# master_board.net
KiCad netlist of a schematic drawn in EAGLE
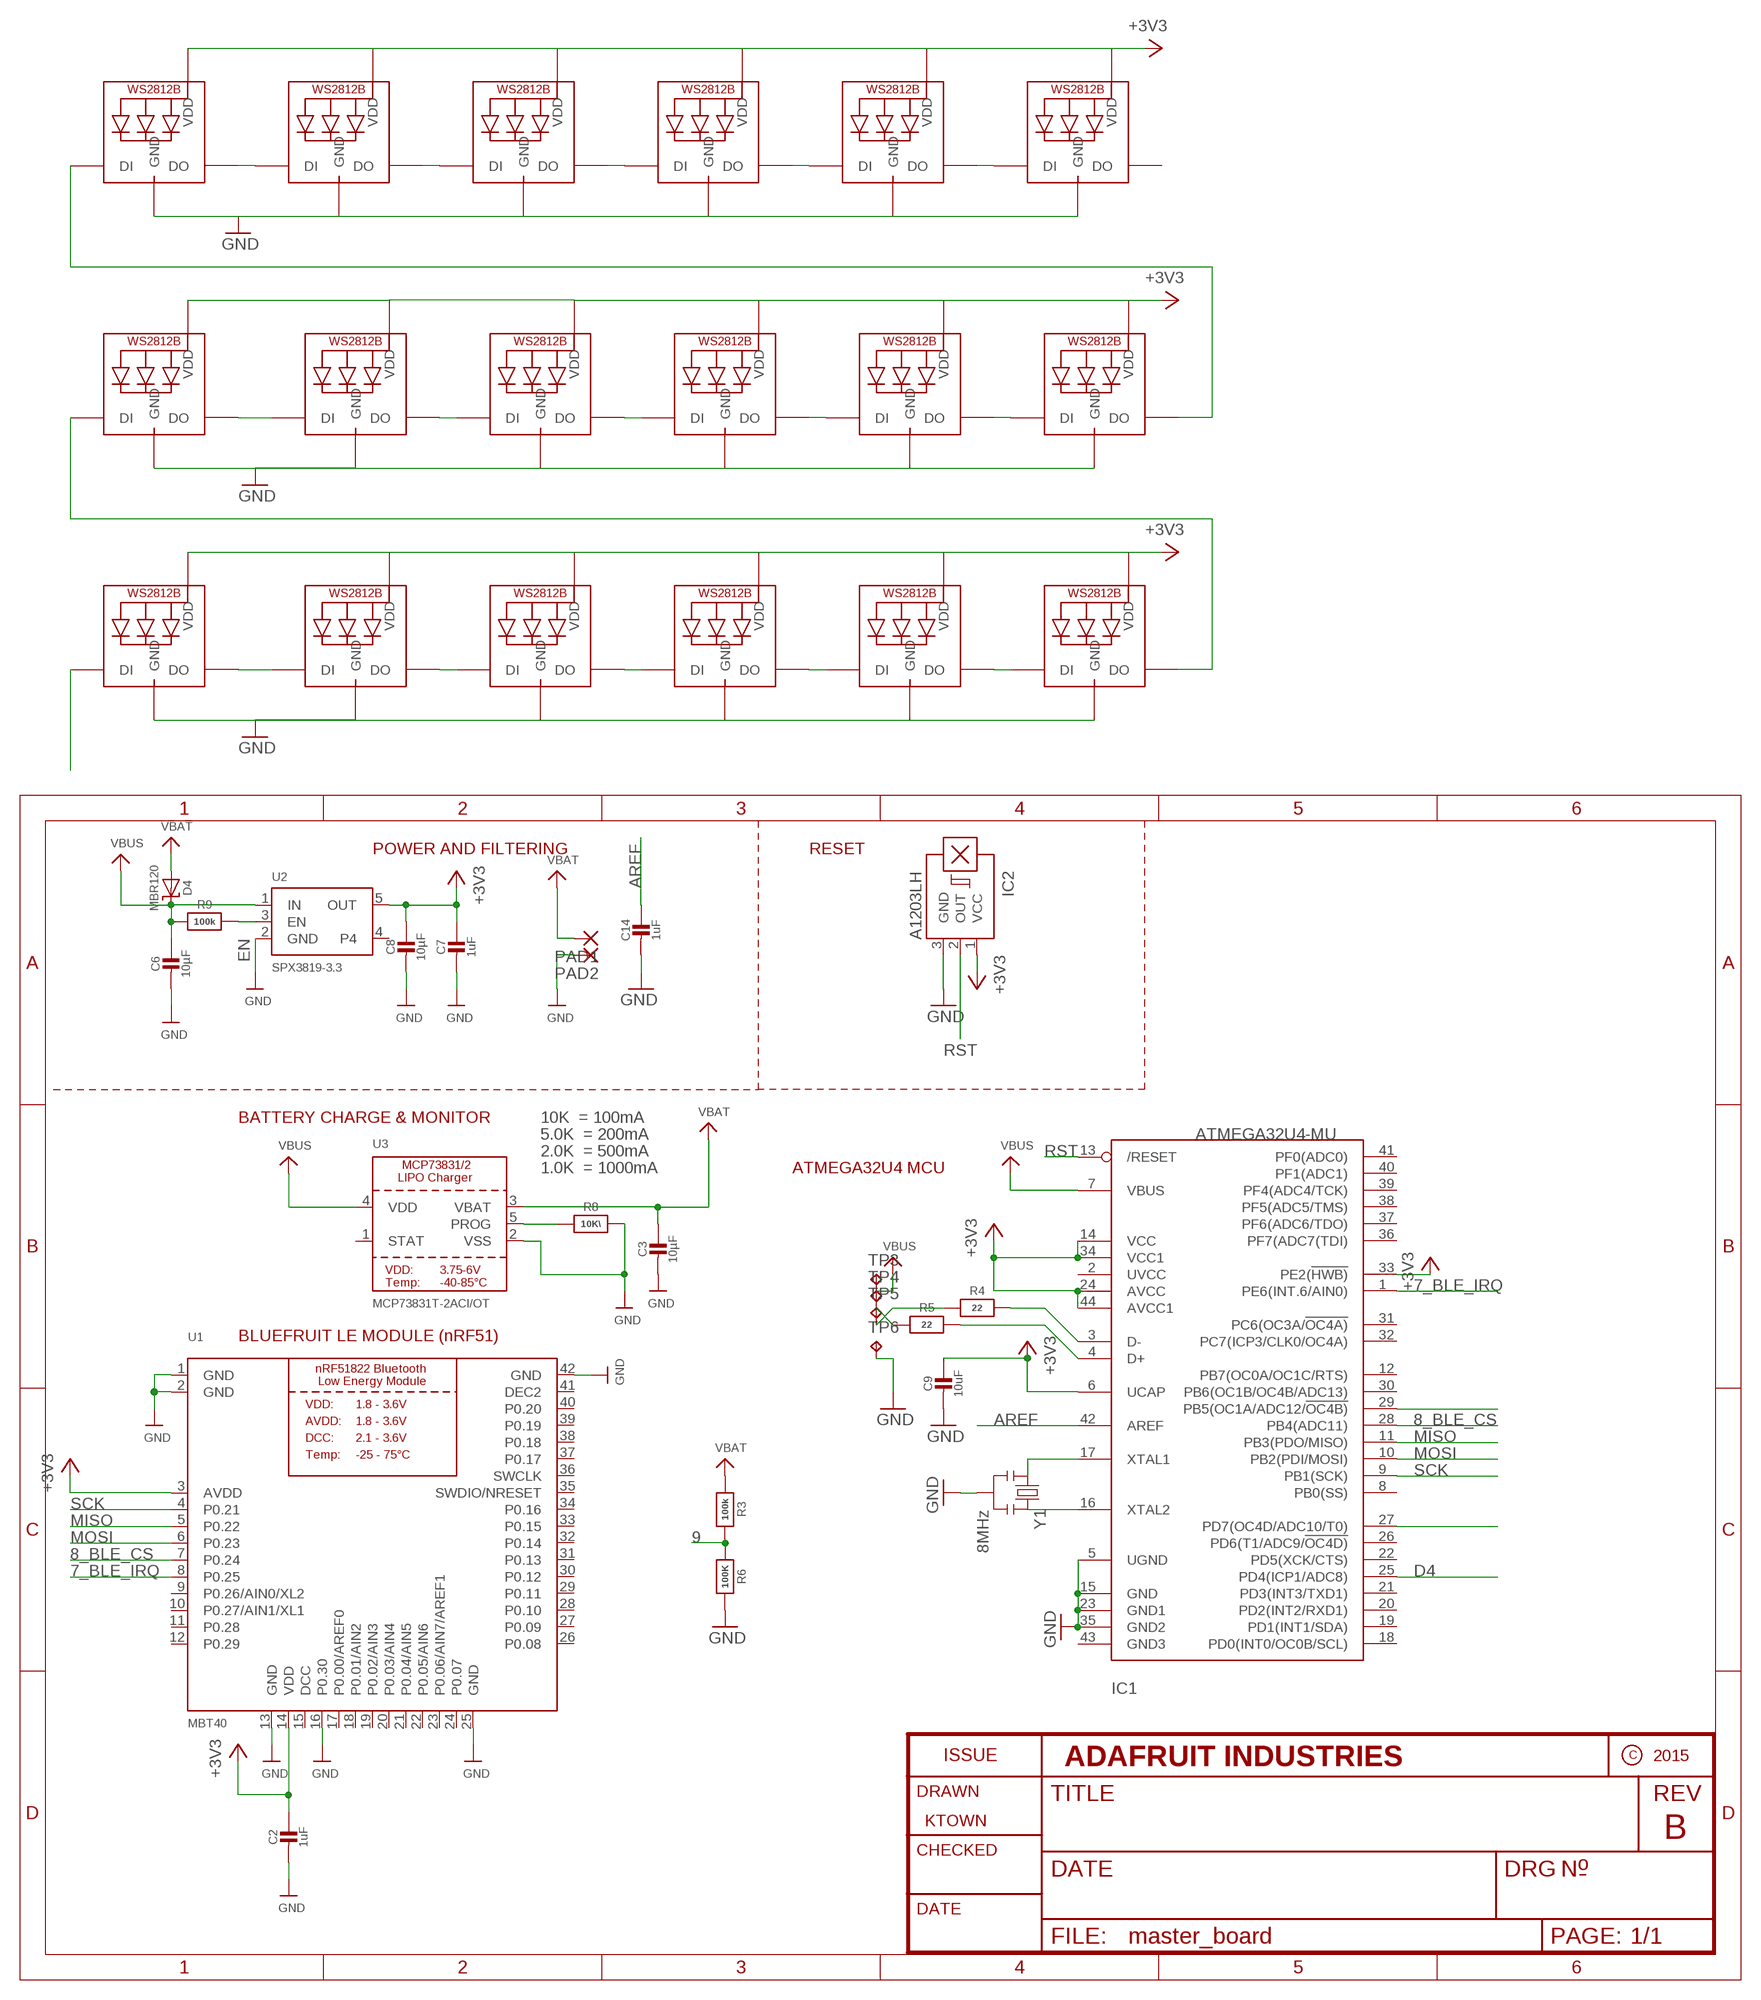
[diagram p0: schematic, sheet 1]

(export (version "E")
  (design (tool "Eeschema 10.0.6"))
  (components
    (comp (ref "C2")
      (value "1uF")
      (footprint "eagle-import:0805-NO")
      (libsource (lib "eagle-import") (part "CAP_CERAMIC0805-NOOUTLINE"))
    )
    (comp (ref "C3")
      (value "10µF")
      (footprint "eagle-import:0805-NO")
      (libsource (lib "eagle-import") (part "CAP_CERAMIC0805-NOOUTLINE"))
    )
    (comp (ref "C6")
      (value "10µF")
      (footprint "eagle-import:0805-NO")
      (libsource (lib "eagle-import") (part "CAP_CERAMIC0805-NOOUTLINE"))
    )
    (comp (ref "C7")
      (value "1uF")
      (footprint "eagle-import:0603-NO")
      (libsource (lib "eagle-import") (part "CAP_CERAMIC0603_NO"))
    )
    (comp (ref "C8")
      (value "10µF")
      (footprint "eagle-import:0805-NO")
      (libsource (lib "eagle-import") (part "CAP_CERAMIC0805-NOOUTLINE"))
    )
    (comp (ref "C9")
      (value "10uF")
      (footprint "eagle-import:0805-NO")
      (libsource (lib "eagle-import") (part "CAP_CERAMIC0805-NOOUTLINE"))
    )
    (comp (ref "C14")
      (value "1uF")
      (footprint "eagle-import:0603-NO")
      (libsource (lib "eagle-import") (part "CAP_CERAMIC0603_NO"))
    )
    (comp (ref "D4")
      (value "MBR120")
      (footprint "eagle-import:SOD-123")
      (libsource (lib "eagle-import") (part "DIODE-SCHOTTKYSOD-123"))
    )
    (comp (ref "IC1")
      (value "ATMEGA32U4-MU")
      (footprint "eagle-import:TQFN44_7MM")
      (libsource (lib "eagle-import") (part "ATMEGA32U4-MU"))
    )
    (comp (ref "IC2")
      (value "A1203LH")
      (footprint "eagle-import:SOT23-W")
      (fields (field (name "MF") "ALLEGRO MICROSYSTEMS, INC.") (field (name "MPN") "A1203LLHLT-T"))
      (libsource (lib "eagle-import") (part "A12?LH03"))
    )
    (comp (ref "LED1")
      (value "WS2812B3535")
      (footprint "eagle-import:LED3535")
      (libsource (lib "eagle-import") (part "WS2812B3535"))
    )
    (comp (ref "LED2")
      (value "WS2812B3535")
      (footprint "eagle-import:LED3535")
      (libsource (lib "eagle-import") (part "WS2812B3535"))
    )
    (comp (ref "LED3")
      (value "WS2812B3535")
      (footprint "eagle-import:LED3535")
      (libsource (lib "eagle-import") (part "WS2812B3535"))
    )
    (comp (ref "LED4")
      (value "WS2812B3535")
      (footprint "eagle-import:LED3535")
      (libsource (lib "eagle-import") (part "WS2812B3535"))
    )
    (comp (ref "LED5")
      (value "WS2812B3535")
      (footprint "eagle-import:LED3535")
      (libsource (lib "eagle-import") (part "WS2812B3535"))
    )
    (comp (ref "LED6")
      (value "WS2812B3535")
      (footprint "eagle-import:LED3535")
      (libsource (lib "eagle-import") (part "WS2812B3535"))
    )
    (comp (ref "LED7")
      (value "WS2812B3535")
      (footprint "eagle-import:LED3535")
      (libsource (lib "eagle-import") (part "WS2812B3535"))
    )
    (comp (ref "LED8")
      (value "WS2812B3535")
      (footprint "eagle-import:LED3535")
      (libsource (lib "eagle-import") (part "WS2812B3535"))
    )
    (comp (ref "LED9")
      (value "WS2812B3535")
      (footprint "eagle-import:LED3535")
      (libsource (lib "eagle-import") (part "WS2812B3535"))
    )
    (comp (ref "LED10")
      (value "WS2812B3535")
      (footprint "eagle-import:LED3535")
      (libsource (lib "eagle-import") (part "WS2812B3535"))
    )
    (comp (ref "LED11")
      (value "WS2812B3535")
      (footprint "eagle-import:LED3535")
      (libsource (lib "eagle-import") (part "WS2812B3535"))
    )
    (comp (ref "LED12")
      (value "WS2812B3535")
      (footprint "eagle-import:LED3535")
      (libsource (lib "eagle-import") (part "WS2812B3535"))
    )
    (comp (ref "LED13")
      (value "WS2812B3535")
      (footprint "eagle-import:LED3535")
      (libsource (lib "eagle-import") (part "WS2812B3535"))
    )
    (comp (ref "LED14")
      (value "WS2812B3535")
      (footprint "eagle-import:LED3535")
      (libsource (lib "eagle-import") (part "WS2812B3535"))
    )
    (comp (ref "LED15")
      (value "WS2812B3535")
      (footprint "eagle-import:LED3535")
      (libsource (lib "eagle-import") (part "WS2812B3535"))
    )
    (comp (ref "LED16")
      (value "WS2812B3535")
      (footprint "eagle-import:LED3535")
      (libsource (lib "eagle-import") (part "WS2812B3535"))
    )
    (comp (ref "LED17")
      (value "WS2812B3535")
      (footprint "eagle-import:LED3535")
      (libsource (lib "eagle-import") (part "WS2812B3535"))
    )
    (comp (ref "LED18")
      (value "WS2812B3535")
      (footprint "eagle-import:LED3535")
      (libsource (lib "eagle-import") (part "WS2812B3535"))
    )
    (comp (ref "PAD1")
      (value "2,54/1,1")
      (footprint "eagle-import:2,54_1,1")
      (libsource (lib "eagle-import") (part "2,54/1,1"))
    )
    (comp (ref "PAD2")
      (value "2,54/1,1")
      (footprint "eagle-import:2,54_1,1")
      (libsource (lib "eagle-import") (part "2,54/1,1"))
    )
    (comp (ref "R3")
      (value "100k")
      (footprint "eagle-import:0603-NO")
      (libsource (lib "eagle-import") (part "RESISTOR_0603_NOOUT"))
    )
    (comp (ref "R4")
      (value "22")
      (footprint "eagle-import:0603-NO")
      (libsource (lib "eagle-import") (part "RESISTOR_0603_NOOUT"))
    )
    (comp (ref "R5")
      (value "22")
      (footprint "eagle-import:0603-NO")
      (libsource (lib "eagle-import") (part "RESISTOR_0603_NOOUT"))
    )
    (comp (ref "R6")
      (value "100K")
      (footprint "eagle-import:_0603MP")
      (libsource (lib "eagle-import") (part "RESISTOR_0603MP"))
    )
    (comp (ref "R8")
      (value "10K\\")
      (footprint "eagle-import:0603-NO")
      (libsource (lib "eagle-import") (part "RESISTOR_0603_NOOUT"))
    )
    (comp (ref "R9")
      (value "100k")
      (footprint "eagle-import:0603-NO")
      (libsource (lib "eagle-import") (part "RESISTOR_0603_NOOUT"))
    )
    (comp (ref "TP3")
      (value "TPTP06SQ")
      (footprint "eagle-import:TP06SQ")
      (libsource (lib "eagle-import") (part "TPTP06SQ"))
    )
    (comp (ref "TP4")
      (value "TPTP06SQ")
      (footprint "eagle-import:TP06SQ")
      (libsource (lib "eagle-import") (part "TPTP06SQ"))
    )
    (comp (ref "TP5")
      (value "TPTP06SQ")
      (footprint "eagle-import:TP06SQ")
      (libsource (lib "eagle-import") (part "TPTP06SQ"))
    )
    (comp (ref "TP6")
      (value "TPTP06SQ")
      (footprint "eagle-import:TP06SQ")
      (libsource (lib "eagle-import") (part "TPTP06SQ"))
    )
    (comp (ref "U1")
      (value "MBT40")
      (footprint "eagle-import:BLE_MODULE_RAYTAC_MDBT40")
      (libsource (lib "eagle-import") (part "NRF51822_MODULE_MDBT40"))
    )
    (comp (ref "U2")
      (value "SPX3819-3.3")
      (footprint "eagle-import:SOT23-5")
      (libsource (lib "eagle-import") (part "VREG_SOT23-5"))
    )
    (comp (ref "U3")
      (value "MCP73831T-2ACI/OT")
      (footprint "eagle-import:SOT23-5")
      (libsource (lib "eagle-import") (part "MCP73831/2"))
    )
    (comp (ref "Y1")
      (value "8MHz")
      (footprint "eagle-import:RESONATOR-SMD")
      (libsource (lib "eagle-import") (part "RESONATORSMD"))
    )
  )
  (nets
    (net (code "1") (name "+3V3") (class "Default")
      (node (ref "C2") (pin "1") (pinfunction "1_1") (pintype "passive"))
      (node (ref "C7") (pin "1") (pinfunction "1_1") (pintype "passive"))
      (node (ref "C8") (pin "1") (pinfunction "1_1") (pintype "passive"))
      (node (ref "C9") (pin "1") (pinfunction "1_1") (pintype "passive"))
      (node (ref "IC1") (pin "14") (pinfunction "VCC_14") (pintype "bidirectional"))
      (node (ref "IC1") (pin "24") (pinfunction "AVCC_24") (pintype "bidirectional"))
      (node (ref "IC1") (pin "33") (pinfunction "PE2(~{HWB})_33") (pintype "bidirectional"))
      (node (ref "IC1") (pin "34") (pinfunction "VCC1_34") (pintype "bidirectional"))
      (node (ref "IC1") (pin "44") (pinfunction "AVCC1_44") (pintype "bidirectional"))
      (node (ref "IC1") (pin "6") (pinfunction "UCAP_6") (pintype "bidirectional"))
      (node (ref "IC2") (pin "1") (pinfunction "VCC_1") (pintype "power_in"))
      (node (ref "LED1") (pin "2") (pinfunction "VDD_2") (pintype "power_in"))
      (node (ref "LED10") (pin "2") (pinfunction "VDD_2") (pintype "power_in"))
      (node (ref "LED11") (pin "2") (pinfunction "VDD_2") (pintype "power_in"))
      (node (ref "LED12") (pin "2") (pinfunction "VDD_2") (pintype "power_in"))
      (node (ref "LED13") (pin "2") (pinfunction "VDD_2") (pintype "power_in"))
      (node (ref "LED14") (pin "2") (pinfunction "VDD_2") (pintype "power_in"))
      (node (ref "LED15") (pin "2") (pinfunction "VDD_2") (pintype "power_in"))
      (node (ref "LED16") (pin "2") (pinfunction "VDD_2") (pintype "power_in"))
      (node (ref "LED17") (pin "2") (pinfunction "VDD_2") (pintype "power_in"))
      (node (ref "LED18") (pin "2") (pinfunction "VDD_2") (pintype "power_in"))
      (node (ref "LED2") (pin "2") (pinfunction "VDD_2") (pintype "power_in"))
      (node (ref "LED3") (pin "2") (pinfunction "VDD_2") (pintype "power_in"))
      (node (ref "LED4") (pin "2") (pinfunction "VDD_2") (pintype "power_in"))
      (node (ref "LED5") (pin "2") (pinfunction "VDD_2") (pintype "power_in"))
      (node (ref "LED6") (pin "2") (pinfunction "VDD_2") (pintype "power_in"))
      (node (ref "LED7") (pin "2") (pinfunction "VDD_2") (pintype "power_in"))
      (node (ref "LED8") (pin "2") (pinfunction "VDD_2") (pintype "power_in"))
      (node (ref "LED9") (pin "2") (pinfunction "VDD_2") (pintype "power_in"))
      (node (ref "U1") (pin "14") (pinfunction "VDD_14") (pintype "power_in"))
      (node (ref "U1") (pin "3") (pinfunction "AVDD_3") (pintype "power_in"))
      (node (ref "U2") (pin "5") (pinfunction "OUT_5") (pintype "power_in"))
    )
    (net (code "2") (name "/6") (class "Default")
      (node (ref "IC1") (pin "27") (pinfunction "PD7(OC4D/ADC10/T0)_27") (pintype "bidirectional"))
      (node (ref "LED1") (pin "1") (pinfunction "DI_1") (pintype "input"))
    )
    (net (code "3") (name "/7_BLE_IRQ") (class "Default")
      (node (ref "IC1") (pin "1") (pinfunction "PE6(INT.6/AIN0)_1") (pintype "bidirectional"))
      (node (ref "U1") (pin "8") (pinfunction "P0.25_8") (pintype "bidirectional"))
    )
    (net (code "4") (name "/8_BLE_CS") (class "Default")
      (node (ref "IC1") (pin "28") (pinfunction "PB4(ADC11)_28") (pintype "bidirectional"))
      (node (ref "U1") (pin "7") (pinfunction "P0.24_7") (pintype "bidirectional"))
    )
    (net (code "5") (name "/9") (class "Default")
      (node (ref "IC1") (pin "29") (pinfunction "PB5(OC1A/ADC12/~{OC4B})_29") (pintype "bidirectional"))
      (node (ref "R3") (pin "2") (pinfunction "2_2") (pintype "passive"))
      (node (ref "R6") (pin "1") (pinfunction "1_1") (pintype "passive"))
    )
    (net (code "6") (name "/AREF") (class "Default")
      (node (ref "C14") (pin "1") (pinfunction "1_1") (pintype "passive"))
      (node (ref "IC1") (pin "42") (pinfunction "AREF_42") (pintype "bidirectional"))
    )
    (net (code "7") (name "/D4") (class "Default")
      (node (ref "IC1") (pin "25") (pinfunction "PD4(ICP1/ADC8)_25") (pintype "bidirectional"))
    )
    (net (code "8") (name "/DCC") (class "Default")
      (node (ref "U1") (pin "15") (pinfunction "DCC_15") (pintype "power_in"))
    )
    (net (code "9") (name "/DEC2") (class "Default")
      (node (ref "U1") (pin "41") (pinfunction "DEC2_41") (pintype "power_in"))
    )
    (net (code "10") (name "/EN") (class "Default")
      (node (ref "R9") (pin "2") (pinfunction "2_2") (pintype "passive"))
      (node (ref "U2") (pin "3") (pinfunction "EN_3") (pintype "input"))
    )
    (net (code "11") (name "/MISO") (class "Default")
      (node (ref "IC1") (pin "11") (pinfunction "PB3(PDO/MISO)_11") (pintype "bidirectional"))
      (node (ref "U1") (pin "5") (pinfunction "P0.22_5") (pintype "bidirectional"))
    )
    (net (code "12") (name "/MOSI") (class "Default")
      (node (ref "IC1") (pin "10") (pinfunction "PB2(PDI/MOSI)_10") (pintype "bidirectional"))
      (node (ref "U1") (pin "6") (pinfunction "P0.23_6") (pintype "bidirectional"))
    )
    (net (code "13") (name "/RST") (class "Default")
      (node (ref "IC1") (pin "13") (pinfunction "/RESET_13") (pintype "bidirectional"))
      (node (ref "IC2") (pin "2") (pinfunction "OUT_2") (pintype "output"))
    )
    (net (code "14") (name "/SCK") (class "Default")
      (node (ref "IC1") (pin "9") (pinfunction "PB1(SCK)_9") (pintype "bidirectional"))
      (node (ref "U1") (pin "4") (pinfunction "P0.21_4") (pintype "bidirectional"))
    )
    (net (code "15") (name "GND") (class "Default")
      (node (ref "C14") (pin "2") (pinfunction "2_2") (pintype "passive"))
      (node (ref "C2") (pin "2") (pinfunction "2_2") (pintype "passive"))
      (node (ref "C3") (pin "2") (pinfunction "2_2") (pintype "passive"))
      (node (ref "C6") (pin "2") (pinfunction "2_2") (pintype "passive"))
      (node (ref "C7") (pin "2") (pinfunction "2_2") (pintype "passive"))
      (node (ref "C8") (pin "2") (pinfunction "2_2") (pintype "passive"))
      (node (ref "C9") (pin "2") (pinfunction "2_2") (pintype "passive"))
      (node (ref "IC1") (pin "15") (pinfunction "GND_15") (pintype "bidirectional"))
      (node (ref "IC1") (pin "23") (pinfunction "GND1_23") (pintype "bidirectional"))
      (node (ref "IC1") (pin "35") (pinfunction "GND2_35") (pintype "bidirectional"))
      (node (ref "IC1") (pin "5") (pinfunction "UGND_5") (pintype "bidirectional"))
      (node (ref "IC2") (pin "3") (pinfunction "GND_3") (pintype "power_in"))
      (node (ref "LED1") (pin "4") (pinfunction "GND_4") (pintype "power_in"))
      (node (ref "LED10") (pin "4") (pinfunction "GND_4") (pintype "power_in"))
      (node (ref "LED11") (pin "4") (pinfunction "GND_4") (pintype "power_in"))
      (node (ref "LED12") (pin "4") (pinfunction "GND_4") (pintype "power_in"))
      (node (ref "LED13") (pin "4") (pinfunction "GND_4") (pintype "power_in"))
      (node (ref "LED14") (pin "4") (pinfunction "GND_4") (pintype "power_in"))
      (node (ref "LED15") (pin "4") (pinfunction "GND_4") (pintype "power_in"))
      (node (ref "LED16") (pin "4") (pinfunction "GND_4") (pintype "power_in"))
      (node (ref "LED17") (pin "4") (pinfunction "GND_4") (pintype "power_in"))
      (node (ref "LED18") (pin "4") (pinfunction "GND_4") (pintype "power_in"))
      (node (ref "LED2") (pin "4") (pinfunction "GND_4") (pintype "power_in"))
      (node (ref "LED3") (pin "4") (pinfunction "GND_4") (pintype "power_in"))
      (node (ref "LED4") (pin "4") (pinfunction "GND_4") (pintype "power_in"))
      (node (ref "LED5") (pin "4") (pinfunction "GND_4") (pintype "power_in"))
      (node (ref "LED6") (pin "4") (pinfunction "GND_4") (pintype "power_in"))
      (node (ref "LED7") (pin "4") (pinfunction "GND_4") (pintype "power_in"))
      (node (ref "LED8") (pin "4") (pinfunction "GND_4") (pintype "power_in"))
      (node (ref "LED9") (pin "4") (pinfunction "GND_4") (pintype "power_in"))
      (node (ref "PAD2") (pin "1") (pinfunction "P_1") (pintype "passive"))
      (node (ref "R6") (pin "2") (pinfunction "2_2") (pintype "passive"))
      (node (ref "R8") (pin "2") (pinfunction "2_2") (pintype "passive"))
      (node (ref "TP6") (pin "TP") (pinfunction "TP_TP") (pintype "input"))
      (node (ref "U1") (pin "1") (pinfunction "GND_1") (pintype "power_in"))
      (node (ref "U1") (pin "13") (pinfunction "GND_13") (pintype "power_in"))
      (node (ref "U1") (pin "16") (pinfunction "P0.30_16") (pintype "bidirectional"))
      (node (ref "U1") (pin "2") (pinfunction "GND_2") (pintype "power_in"))
      (node (ref "U1") (pin "25") (pinfunction "GND_25") (pintype "power_in"))
      (node (ref "U1") (pin "42") (pinfunction "GND_42") (pintype "power_in"))
      (node (ref "U2") (pin "2") (pinfunction "GND_2") (pintype "power_in"))
      (node (ref "U3") (pin "2") (pinfunction "VSS_2") (pintype "power_in"))
      (node (ref "Y1") (pin "2") (pinfunction "2_2") (pintype "passive"))
    )
    (net (code "16") (name "Net-(IC1-D+)") (class "Default")
      (node (ref "IC1") (pin "4") (pinfunction "D+_4") (pintype "bidirectional"))
      (node (ref "R5") (pin "2") (pinfunction "2_2") (pintype "passive"))
    )
    (net (code "17") (name "Net-(IC1-D-)") (class "Default")
      (node (ref "IC1") (pin "3") (pinfunction "D-_3") (pintype "bidirectional"))
      (node (ref "R4") (pin "2") (pinfunction "2_2") (pintype "passive"))
    )
    (net (code "18") (name "Net-(IC1-XTAL1)") (class "Default")
      (node (ref "IC1") (pin "17") (pinfunction "XTAL1_17") (pintype "bidirectional"))
      (node (ref "Y1") (pin "1") (pinfunction "1_1") (pintype "passive"))
    )
    (net (code "19") (name "Net-(IC1-XTAL2)") (class "Default")
      (node (ref "IC1") (pin "16") (pinfunction "XTAL2_16") (pintype "bidirectional"))
      (node (ref "Y1") (pin "3") (pinfunction "3_3") (pintype "passive"))
    )
    (net (code "20") (name "Net-(LED1-DO)") (class "Default")
      (node (ref "LED1") (pin "3") (pinfunction "DO_3") (pintype "output"))
      (node (ref "LED2") (pin "1") (pinfunction "DI_1") (pintype "input"))
    )
    (net (code "21") (name "Net-(LED2-DO)") (class "Default")
      (node (ref "LED2") (pin "3") (pinfunction "DO_3") (pintype "output"))
      (node (ref "LED3") (pin "1") (pinfunction "DI_1") (pintype "input"))
    )
    (net (code "22") (name "Net-(LED3-DO)") (class "Default")
      (node (ref "LED3") (pin "3") (pinfunction "DO_3") (pintype "output"))
      (node (ref "LED4") (pin "1") (pinfunction "DI_1") (pintype "input"))
    )
    (net (code "23") (name "Net-(LED4-DO)") (class "Default")
      (node (ref "LED4") (pin "3") (pinfunction "DO_3") (pintype "output"))
      (node (ref "LED5") (pin "1") (pinfunction "DI_1") (pintype "input"))
    )
    (net (code "24") (name "Net-(LED5-DO)") (class "Default")
      (node (ref "LED5") (pin "3") (pinfunction "DO_3") (pintype "output"))
      (node (ref "LED6") (pin "1") (pinfunction "DI_1") (pintype "input"))
    )
    (net (code "25") (name "Net-(LED6-DO)") (class "Default")
      (node (ref "LED6") (pin "3") (pinfunction "DO_3") (pintype "output"))
      (node (ref "LED7") (pin "1") (pinfunction "DI_1") (pintype "input"))
    )
    (net (code "26") (name "Net-(LED7-DO)") (class "Default")
      (node (ref "LED7") (pin "3") (pinfunction "DO_3") (pintype "output"))
      (node (ref "LED8") (pin "1") (pinfunction "DI_1") (pintype "input"))
    )
    (net (code "27") (name "Net-(LED8-DO)") (class "Default")
      (node (ref "LED8") (pin "3") (pinfunction "DO_3") (pintype "output"))
      (node (ref "LED9") (pin "1") (pinfunction "DI_1") (pintype "input"))
    )
    (net (code "28") (name "Net-(LED10-DI)") (class "Default")
      (node (ref "LED10") (pin "1") (pinfunction "DI_1") (pintype "input"))
      (node (ref "LED9") (pin "3") (pinfunction "DO_3") (pintype "output"))
    )
    (net (code "29") (name "Net-(LED10-DO)") (class "Default")
      (node (ref "LED10") (pin "3") (pinfunction "DO_3") (pintype "output"))
      (node (ref "LED11") (pin "1") (pinfunction "DI_1") (pintype "input"))
    )
    (net (code "30") (name "Net-(LED11-DO)") (class "Default")
      (node (ref "LED11") (pin "3") (pinfunction "DO_3") (pintype "output"))
      (node (ref "LED12") (pin "1") (pinfunction "DI_1") (pintype "input"))
    )
    (net (code "31") (name "Net-(LED12-DO)") (class "Default")
      (node (ref "LED12") (pin "3") (pinfunction "DO_3") (pintype "output"))
      (node (ref "LED13") (pin "1") (pinfunction "DI_1") (pintype "input"))
    )
    (net (code "32") (name "Net-(LED13-DO)") (class "Default")
      (node (ref "LED13") (pin "3") (pinfunction "DO_3") (pintype "output"))
      (node (ref "LED14") (pin "1") (pinfunction "DI_1") (pintype "input"))
    )
    (net (code "33") (name "Net-(LED14-DO)") (class "Default")
      (node (ref "LED14") (pin "3") (pinfunction "DO_3") (pintype "output"))
      (node (ref "LED15") (pin "1") (pinfunction "DI_1") (pintype "input"))
    )
    (net (code "34") (name "Net-(LED15-DO)") (class "Default")
      (node (ref "LED15") (pin "3") (pinfunction "DO_3") (pintype "output"))
      (node (ref "LED16") (pin "1") (pinfunction "DI_1") (pintype "input"))
    )
    (net (code "35") (name "Net-(LED16-DO)") (class "Default")
      (node (ref "LED16") (pin "3") (pinfunction "DO_3") (pintype "output"))
      (node (ref "LED17") (pin "1") (pinfunction "DI_1") (pintype "input"))
    )
    (net (code "36") (name "Net-(LED17-DO)") (class "Default")
      (node (ref "LED17") (pin "3") (pinfunction "DO_3") (pintype "output"))
      (node (ref "LED18") (pin "1") (pinfunction "DI_1") (pintype "input"))
    )
    (net (code "37") (name "Net-(R4-Pad1)") (class "Default")
      (node (ref "R4") (pin "1") (pinfunction "1_1") (pintype "passive"))
      (node (ref "TP5") (pin "TP") (pinfunction "TP_TP") (pintype "input"))
    )
    (net (code "38") (name "Net-(R5-Pad1)") (class "Default")
      (node (ref "R5") (pin "1") (pinfunction "1_1") (pintype "passive"))
      (node (ref "TP4") (pin "TP") (pinfunction "TP_TP") (pintype "input"))
    )
    (net (code "39") (name "Net-(U3-PROG)") (class "Default")
      (node (ref "R8") (pin "1") (pinfunction "1_1") (pintype "passive"))
      (node (ref "U3") (pin "5") (pinfunction "PROG_5") (pintype "input"))
    )
    (net (code "40") (name "VBAT") (class "Default")
      (node (ref "C3") (pin "1") (pinfunction "1_1") (pintype "passive"))
      (node (ref "D4") (pin "A") (pinfunction "A_A") (pintype "passive"))
      (node (ref "PAD1") (pin "1") (pinfunction "P_1") (pintype "passive"))
      (node (ref "R3") (pin "1") (pinfunction "1_1") (pintype "passive"))
      (node (ref "U3") (pin "3") (pinfunction "VBAT_3") (pintype "power_in"))
    )
    (net (code "41") (name "VBUS") (class "Default")
      (node (ref "C6") (pin "1") (pinfunction "1_1") (pintype "passive"))
      (node (ref "D4") (pin "C") (pinfunction "C_C") (pintype "passive"))
      (node (ref "IC1") (pin "7") (pinfunction "VBUS_7") (pintype "bidirectional"))
      (node (ref "R9") (pin "1") (pinfunction "1_1") (pintype "passive"))
      (node (ref "TP3") (pin "TP") (pinfunction "TP_TP") (pintype "input"))
      (node (ref "U2") (pin "1") (pinfunction "IN_1") (pintype "power_in"))
      (node (ref "U3") (pin "4") (pinfunction "VDD_4") (pintype "power_in"))
    )
    (net (code "42") (name "unconnected-(IC1-GND3-Pad43)") (class "Default")
      (node (ref "IC1") (pin "43") (pinfunction "GND3_43") (pintype "bidirectional"))
    )
    (net (code "43") (name "unconnected-(IC1-PB0(SS)-Pad8)") (class "Default")
      (node (ref "IC1") (pin "8") (pinfunction "PB0(SS)_8") (pintype "bidirectional"))
    )
    (net (code "44") (name "unconnected-(IC1-PB6(OC1B{slash}OC4B{slash}ADC13)-Pad30)") (class "Default")
      (node (ref "IC1") (pin "30") (pinfunction "PB6(OC1B/OC4B/ADC13)_30") (pintype "bidirectional"))
    )
    (net (code "45") (name "unconnected-(IC1-PB7(OC0A{slash}OC1C{slash}RTS)-Pad12)") (class "Default")
      (node (ref "IC1") (pin "12") (pinfunction "PB7(OC0A/OC1C/RTS)_12") (pintype "bidirectional"))
    )
    (net (code "46") (name "unconnected-(IC1-PC6(OC3A{slash}~{OC4A})-Pad31)") (class "Default")
      (node (ref "IC1") (pin "31") (pinfunction "PC6(OC3A/~{OC4A})_31") (pintype "bidirectional"))
    )
    (net (code "47") (name "unconnected-(IC1-PC7(ICP3{slash}CLK0{slash}OC4A)-Pad32)") (class "Default")
      (node (ref "IC1") (pin "32") (pinfunction "PC7(ICP3/CLK0/OC4A)_32") (pintype "bidirectional"))
    )
    (net (code "48") (name "unconnected-(IC1-PD0(INT0{slash}OC0B{slash}SCL)-Pad18)") (class "Default")
      (node (ref "IC1") (pin "18") (pinfunction "PD0(INT0/OC0B/SCL)_18") (pintype "bidirectional"))
    )
    (net (code "49") (name "unconnected-(IC1-PD1(INT1{slash}SDA)-Pad19)") (class "Default")
      (node (ref "IC1") (pin "19") (pinfunction "PD1(INT1/SDA)_19") (pintype "bidirectional"))
    )
    (net (code "50") (name "unconnected-(IC1-PD2(INT2{slash}RXD1)-Pad20)") (class "Default")
      (node (ref "IC1") (pin "20") (pinfunction "PD2(INT2/RXD1)_20") (pintype "bidirectional"))
    )
    (net (code "51") (name "unconnected-(IC1-PD3(INT3{slash}TXD1)-Pad21)") (class "Default")
      (node (ref "IC1") (pin "21") (pinfunction "PD3(INT3/TXD1)_21") (pintype "bidirectional"))
    )
    (net (code "52") (name "unconnected-(IC1-PD5(XCK{slash}CTS)-Pad22)") (class "Default")
      (node (ref "IC1") (pin "22") (pinfunction "PD5(XCK/CTS)_22") (pintype "bidirectional"))
    )
    (net (code "53") (name "unconnected-(IC1-PD6(T1{slash}ADC9{slash}~{OC4D})-Pad26)") (class "Default")
      (node (ref "IC1") (pin "26") (pinfunction "PD6(T1/ADC9/~{OC4D})_26") (pintype "bidirectional"))
    )
    (net (code "54") (name "unconnected-(IC1-PF0(ADC0)-Pad41)") (class "Default")
      (node (ref "IC1") (pin "41") (pinfunction "PF0(ADC0)_41") (pintype "bidirectional"))
    )
    (net (code "55") (name "unconnected-(IC1-PF1(ADC1)-Pad40)") (class "Default")
      (node (ref "IC1") (pin "40") (pinfunction "PF1(ADC1)_40") (pintype "bidirectional"))
    )
    (net (code "56") (name "unconnected-(IC1-PF4(ADC4{slash}TCK)-Pad39)") (class "Default")
      (node (ref "IC1") (pin "39") (pinfunction "PF4(ADC4/TCK)_39") (pintype "bidirectional"))
    )
    (net (code "57") (name "unconnected-(IC1-PF5(ADC5{slash}TMS)-Pad38)") (class "Default")
      (node (ref "IC1") (pin "38") (pinfunction "PF5(ADC5/TMS)_38") (pintype "bidirectional"))
    )
    (net (code "58") (name "unconnected-(IC1-PF6(ADC6{slash}TDO)-Pad37)") (class "Default")
      (node (ref "IC1") (pin "37") (pinfunction "PF6(ADC6/TDO)_37") (pintype "bidirectional"))
    )
    (net (code "59") (name "unconnected-(IC1-PF7(ADC7(TDI)-Pad36)") (class "Default")
      (node (ref "IC1") (pin "36") (pinfunction "PF7(ADC7(TDI)_36") (pintype "bidirectional"))
    )
    (net (code "60") (name "unconnected-(IC1-UVCC-Pad2)") (class "Default")
      (node (ref "IC1") (pin "2") (pinfunction "UVCC_2") (pintype "bidirectional"))
    )
    (net (code "61") (name "unconnected-(LED18-DO-Pad3)") (class "Default")
      (node (ref "LED18") (pin "3") (pinfunction "DO_3") (pintype "output"))
    )
    (net (code "62") (name "unconnected-(U1-P0.00{slash}AREF0-Pad17)") (class "Default")
      (node (ref "U1") (pin "17") (pinfunction "P0.00/AREF0_17") (pintype "bidirectional"))
    )
    (net (code "63") (name "unconnected-(U1-P0.01{slash}AIN2-Pad18)") (class "Default")
      (node (ref "U1") (pin "18") (pinfunction "P0.01/AIN2_18") (pintype "bidirectional"))
    )
    (net (code "64") (name "unconnected-(U1-P0.02{slash}AIN3-Pad19)") (class "Default")
      (node (ref "U1") (pin "19") (pinfunction "P0.02/AIN3_19") (pintype "bidirectional"))
    )
    (net (code "65") (name "unconnected-(U1-P0.03{slash}AIN4-Pad20)") (class "Default")
      (node (ref "U1") (pin "20") (pinfunction "P0.03/AIN4_20") (pintype "bidirectional"))
    )
    (net (code "66") (name "unconnected-(U1-P0.04{slash}AIN5-Pad21)") (class "Default")
      (node (ref "U1") (pin "21") (pinfunction "P0.04/AIN5_21") (pintype "bidirectional"))
    )
    (net (code "67") (name "unconnected-(U1-P0.05{slash}AIN6-Pad22)") (class "Default")
      (node (ref "U1") (pin "22") (pinfunction "P0.05/AIN6_22") (pintype "bidirectional"))
    )
    (net (code "68") (name "unconnected-(U1-P0.06{slash}AIN7{slash}AREF1-Pad23)") (class "Default")
      (node (ref "U1") (pin "23") (pinfunction "P0.06/AIN7/AREF1_23") (pintype "bidirectional"))
    )
    (net (code "69") (name "unconnected-(U1-P0.07-Pad24)") (class "Default")
      (node (ref "U1") (pin "24") (pinfunction "P0.07_24") (pintype "bidirectional"))
    )
    (net (code "70") (name "unconnected-(U1-P0.08-Pad26)") (class "Default")
      (node (ref "U1") (pin "26") (pinfunction "P0.08_26") (pintype "bidirectional"))
    )
    (net (code "71") (name "unconnected-(U1-P0.09-Pad27)") (class "Default")
      (node (ref "U1") (pin "27") (pinfunction "P0.09_27") (pintype "bidirectional"))
    )
    (net (code "72") (name "unconnected-(U1-P0.10-Pad28)") (class "Default")
      (node (ref "U1") (pin "28") (pinfunction "P0.10_28") (pintype "bidirectional"))
    )
    (net (code "73") (name "unconnected-(U1-P0.11-Pad29)") (class "Default")
      (node (ref "U1") (pin "29") (pinfunction "P0.11_29") (pintype "bidirectional"))
    )
    (net (code "74") (name "unconnected-(U1-P0.12-Pad30)") (class "Default")
      (node (ref "U1") (pin "30") (pinfunction "P0.12_30") (pintype "bidirectional"))
    )
    (net (code "75") (name "unconnected-(U1-P0.13-Pad31)") (class "Default")
      (node (ref "U1") (pin "31") (pinfunction "P0.13_31") (pintype "bidirectional"))
    )
    (net (code "76") (name "unconnected-(U1-P0.14-Pad32)") (class "Default")
      (node (ref "U1") (pin "32") (pinfunction "P0.14_32") (pintype "bidirectional"))
    )
    (net (code "77") (name "unconnected-(U1-P0.15-Pad33)") (class "Default")
      (node (ref "U1") (pin "33") (pinfunction "P0.15_33") (pintype "bidirectional"))
    )
    (net (code "78") (name "unconnected-(U1-P0.16-Pad34)") (class "Default")
      (node (ref "U1") (pin "34") (pinfunction "P0.16_34") (pintype "bidirectional"))
    )
    (net (code "79") (name "unconnected-(U1-P0.17-Pad37)") (class "Default")
      (node (ref "U1") (pin "37") (pinfunction "P0.17_37") (pintype "bidirectional"))
    )
    (net (code "80") (name "unconnected-(U1-P0.18-Pad38)") (class "Default")
      (node (ref "U1") (pin "38") (pinfunction "P0.18_38") (pintype "bidirectional"))
    )
    (net (code "81") (name "unconnected-(U1-P0.19-Pad39)") (class "Default")
      (node (ref "U1") (pin "39") (pinfunction "P0.19_39") (pintype "bidirectional"))
    )
    (net (code "82") (name "unconnected-(U1-P0.20-Pad40)") (class "Default")
      (node (ref "U1") (pin "40") (pinfunction "P0.20_40") (pintype "bidirectional"))
    )
    (net (code "83") (name "unconnected-(U1-P0.26{slash}AIN0{slash}XL2-Pad9)") (class "Default")
      (node (ref "U1") (pin "9") (pinfunction "P0.26/AIN0/XL2_9") (pintype "bidirectional"))
    )
    (net (code "84") (name "unconnected-(U1-P0.27{slash}AIN1{slash}XL1-Pad10)") (class "Default")
      (node (ref "U1") (pin "10") (pinfunction "P0.27/AIN1/XL1_10") (pintype "bidirectional"))
    )
    (net (code "85") (name "unconnected-(U1-P0.28-Pad11)") (class "Default")
      (node (ref "U1") (pin "11") (pinfunction "P0.28_11") (pintype "bidirectional"))
    )
    (net (code "86") (name "unconnected-(U1-P0.29-Pad12)") (class "Default")
      (node (ref "U1") (pin "12") (pinfunction "P0.29_12") (pintype "bidirectional"))
    )
    (net (code "87") (name "unconnected-(U1-SWCLK-Pad36)") (class "Default")
      (node (ref "U1") (pin "36") (pinfunction "SWCLK_36") (pintype "bidirectional"))
    )
    (net (code "88") (name "unconnected-(U1-SWDIO{slash}NRESET-Pad35)") (class "Default")
      (node (ref "U1") (pin "35") (pinfunction "SWDIO/NRESET_35") (pintype "bidirectional"))
    )
    (net (code "89") (name "unconnected-(U2-P4-Pad4)") (class "Default")
      (node (ref "U2") (pin "4") (pinfunction "P4_4") (pintype "bidirectional"))
    )
    (net (code "90") (name "unconnected-(U3-STAT-Pad1)") (class "Default")
      (node (ref "U3") (pin "1") (pinfunction "STAT_1") (pintype "output"))
    )
  )
)
